# DOG_DisplayBreakout_Switched.net
KiCad netlist of a schematic drawn in EAGLE
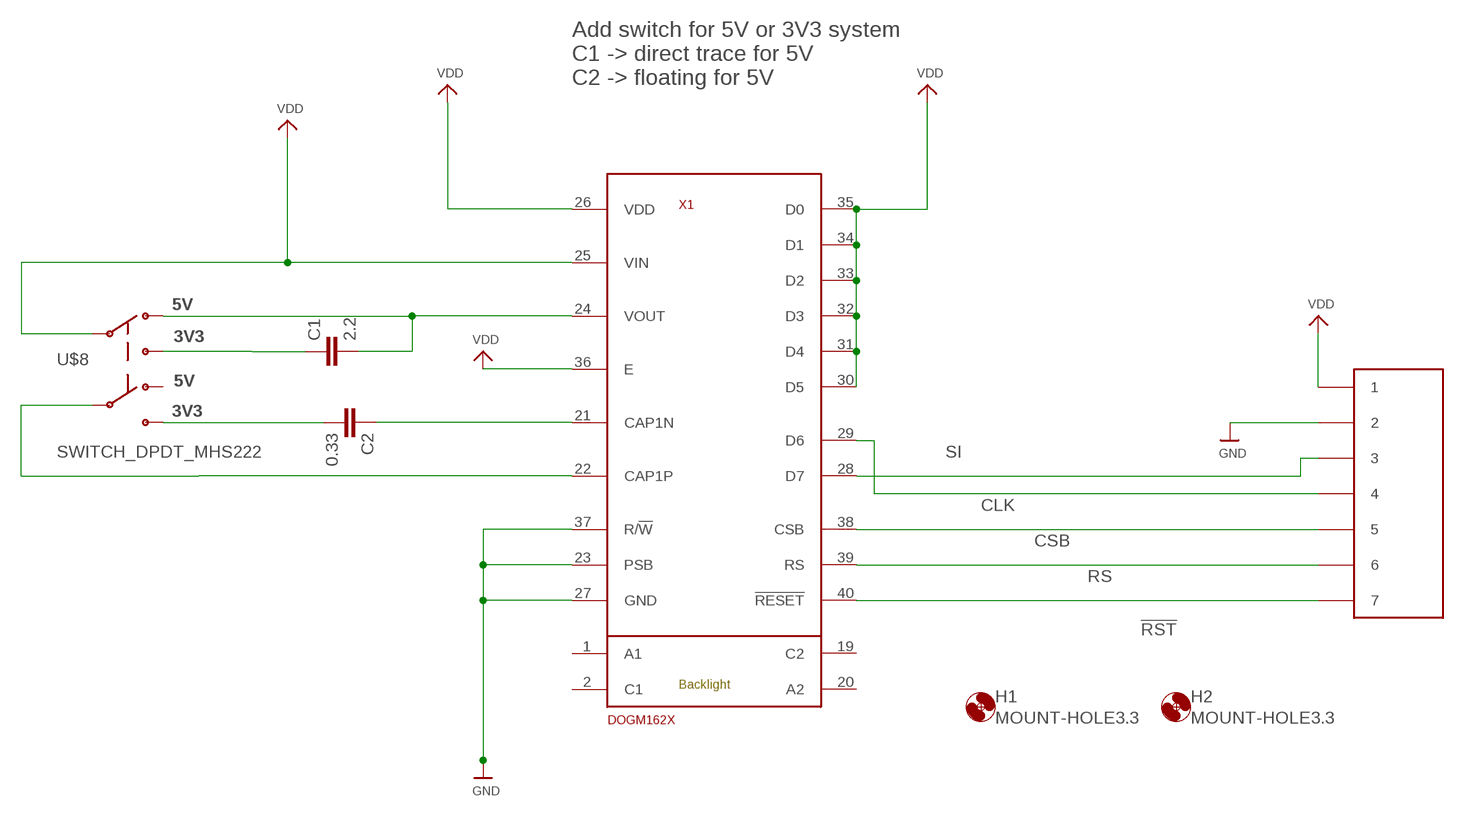
[diagram p0: schematic, sheet 1]

(export (version "E")
  (design (tool "Eeschema 10.0.6"))
  (components
    (comp (ref "C1")
      (value "2.2")
      (footprint "eagle-import:0805_BIGGERPAD-OK")
      (libsource (lib "eagle-import") (part "CAPACITOR0805"))
    )
    (comp (ref "C2")
      (value "0.33")
      (footprint "eagle-import:0805_BIGGERPAD-OK")
      (libsource (lib "eagle-import") (part "CAPACITOR0805"))
    )
    (comp (ref "CN1")
      (value "JST_S7B-PH-K-S")
      (footprint "eagle-import:JST_S7B-PH-K-S")
      (libsource (lib "eagle-import") (part "JST_S7B-PH-K-S"))
    )
    (comp (ref "H1")
      (value "MOUNT-HOLE3.3")
      (footprint "eagle-import:HOLE3,3")
      (libsource (lib "eagle-import") (part "MOUNT-HOLE3.3"))
    )
    (comp (ref "H2")
      (value "MOUNT-HOLE3.3")
      (footprint "eagle-import:HOLE3,3")
      (libsource (lib "eagle-import") (part "MOUNT-HOLE3.3"))
    )
    (comp (ref "U$8")
      (value "SWITCH_DPDT_MHS222")
      (footprint "eagle-import:SWITCH_MHS222")
      (libsource (lib "eagle-import") (part "SWITCH_DPDT_MHS222"))
    )
    (comp (ref "X1")
      (value "DOGM162X")
      (footprint "eagle-import:DOGM162X")
      (libsource (lib "eagle-import") (part "DOGM162X"))
    )
  )
  (nets
    (net (code "1") (name "/CLK") (class "Default")
      (node (ref "CN1") (pin "P4") (pinfunction "4_P4") (pintype "bidirectional"))
      (node (ref "X1") (pin "29") (pinfunction "D6_29") (pintype "bidirectional"))
    )
    (net (code "2") (name "/CSB") (class "Default")
      (node (ref "CN1") (pin "P5") (pinfunction "5_P5") (pintype "bidirectional"))
      (node (ref "X1") (pin "38") (pinfunction "CSB_38") (pintype "bidirectional"))
    )
    (net (code "3") (name "/RS") (class "Default")
      (node (ref "CN1") (pin "P6") (pinfunction "6_P6") (pintype "bidirectional"))
      (node (ref "X1") (pin "39") (pinfunction "RS_39") (pintype "bidirectional"))
    )
    (net (code "4") (name "/SI") (class "Default")
      (node (ref "CN1") (pin "P3") (pinfunction "3_P3") (pintype "bidirectional"))
      (node (ref "X1") (pin "28") (pinfunction "D7_28") (pintype "bidirectional"))
    )
    (net (code "5") (name "/~{RST}") (class "Default")
      (node (ref "CN1") (pin "P7") (pinfunction "7_P7") (pintype "bidirectional"))
      (node (ref "X1") (pin "40") (pinfunction "~{RESET}_40") (pintype "bidirectional"))
    )
    (net (code "6") (name "GND") (class "Default")
      (node (ref "CN1") (pin "P2") (pinfunction "2_P2") (pintype "bidirectional"))
      (node (ref "X1") (pin "23") (pinfunction "PSB_23") (pintype "bidirectional"))
      (node (ref "X1") (pin "27") (pinfunction "GND_27") (pintype "bidirectional"))
      (node (ref "X1") (pin "37") (pinfunction "R/~{W}_37") (pintype "bidirectional"))
    )
    (net (code "7") (name "Net-(U$8-1)") (class "Default")
      (node (ref "C1") (pin "2") (pinfunction "2_2") (pintype "passive"))
      (node (ref "U$8") (pin "P$1") (pinfunction "1_P$1") (pintype "bidirectional"))
      (node (ref "X1") (pin "24") (pinfunction "VOUT_24") (pintype "bidirectional"))
    )
    (net (code "8") (name "Net-(U$8-3)") (class "Default")
      (node (ref "C1") (pin "1") (pinfunction "1_1") (pintype "passive"))
      (node (ref "U$8") (pin "P$3") (pinfunction "3_P$3") (pintype "bidirectional"))
    )
    (net (code "9") (name "Net-(U$8-5)") (class "Default")
      (node (ref "U$8") (pin "P$5") (pinfunction "5_P$5") (pintype "bidirectional"))
      (node (ref "X1") (pin "22") (pinfunction "CAP1P_22") (pintype "bidirectional"))
    )
    (net (code "10") (name "Net-(U$8-6)") (class "Default")
      (node (ref "C2") (pin "2") (pinfunction "2_2") (pintype "passive"))
      (node (ref "U$8") (pin "P$6") (pinfunction "6_P$6") (pintype "bidirectional"))
    )
    (net (code "11") (name "Net-(X1-CAP1N)") (class "Default")
      (node (ref "C2") (pin "1") (pinfunction "1_1") (pintype "passive"))
      (node (ref "X1") (pin "21") (pinfunction "CAP1N_21") (pintype "bidirectional"))
    )
    (net (code "12") (name "VDD") (class "Default")
      (node (ref "CN1") (pin "P1") (pinfunction "1_P1") (pintype "bidirectional"))
      (node (ref "U$8") (pin "P$2") (pinfunction "2_P$2") (pintype "bidirectional"))
      (node (ref "X1") (pin "25") (pinfunction "VIN_25") (pintype "bidirectional"))
      (node (ref "X1") (pin "26") (pinfunction "VDD_26") (pintype "bidirectional"))
      (node (ref "X1") (pin "30") (pinfunction "D5_30") (pintype "bidirectional"))
      (node (ref "X1") (pin "31") (pinfunction "D4_31") (pintype "bidirectional"))
      (node (ref "X1") (pin "32") (pinfunction "D3_32") (pintype "bidirectional"))
      (node (ref "X1") (pin "33") (pinfunction "D2_33") (pintype "bidirectional"))
      (node (ref "X1") (pin "34") (pinfunction "D1_34") (pintype "bidirectional"))
      (node (ref "X1") (pin "35") (pinfunction "D0_35") (pintype "bidirectional"))
      (node (ref "X1") (pin "36") (pinfunction "E_36") (pintype "bidirectional"))
    )
    (net (code "13") (name "unconnected-(U$8-4-PadP$4)") (class "Default")
      (node (ref "U$8") (pin "P$4") (pinfunction "4_P$4") (pintype "bidirectional"))
    )
    (net (code "14") (name "unconnected-(X1-A1-Pad1)") (class "Default")
      (node (ref "X1") (pin "1") (pinfunction "A1_1") (pintype "bidirectional"))
    )
    (net (code "15") (name "unconnected-(X1-A2-Pad20)") (class "Default")
      (node (ref "X1") (pin "20") (pinfunction "A2_20") (pintype "bidirectional"))
    )
    (net (code "16") (name "unconnected-(X1-C1-Pad2)") (class "Default")
      (node (ref "X1") (pin "2") (pinfunction "C1_2") (pintype "bidirectional"))
    )
    (net (code "17") (name "unconnected-(X1-C2-Pad19)") (class "Default")
      (node (ref "X1") (pin "19") (pinfunction "C2_19") (pintype "bidirectional"))
    )
  )
)
